# Wacky_Racer_Schematic.net
KiCad netlist of a schematic drawn in Altium Designer
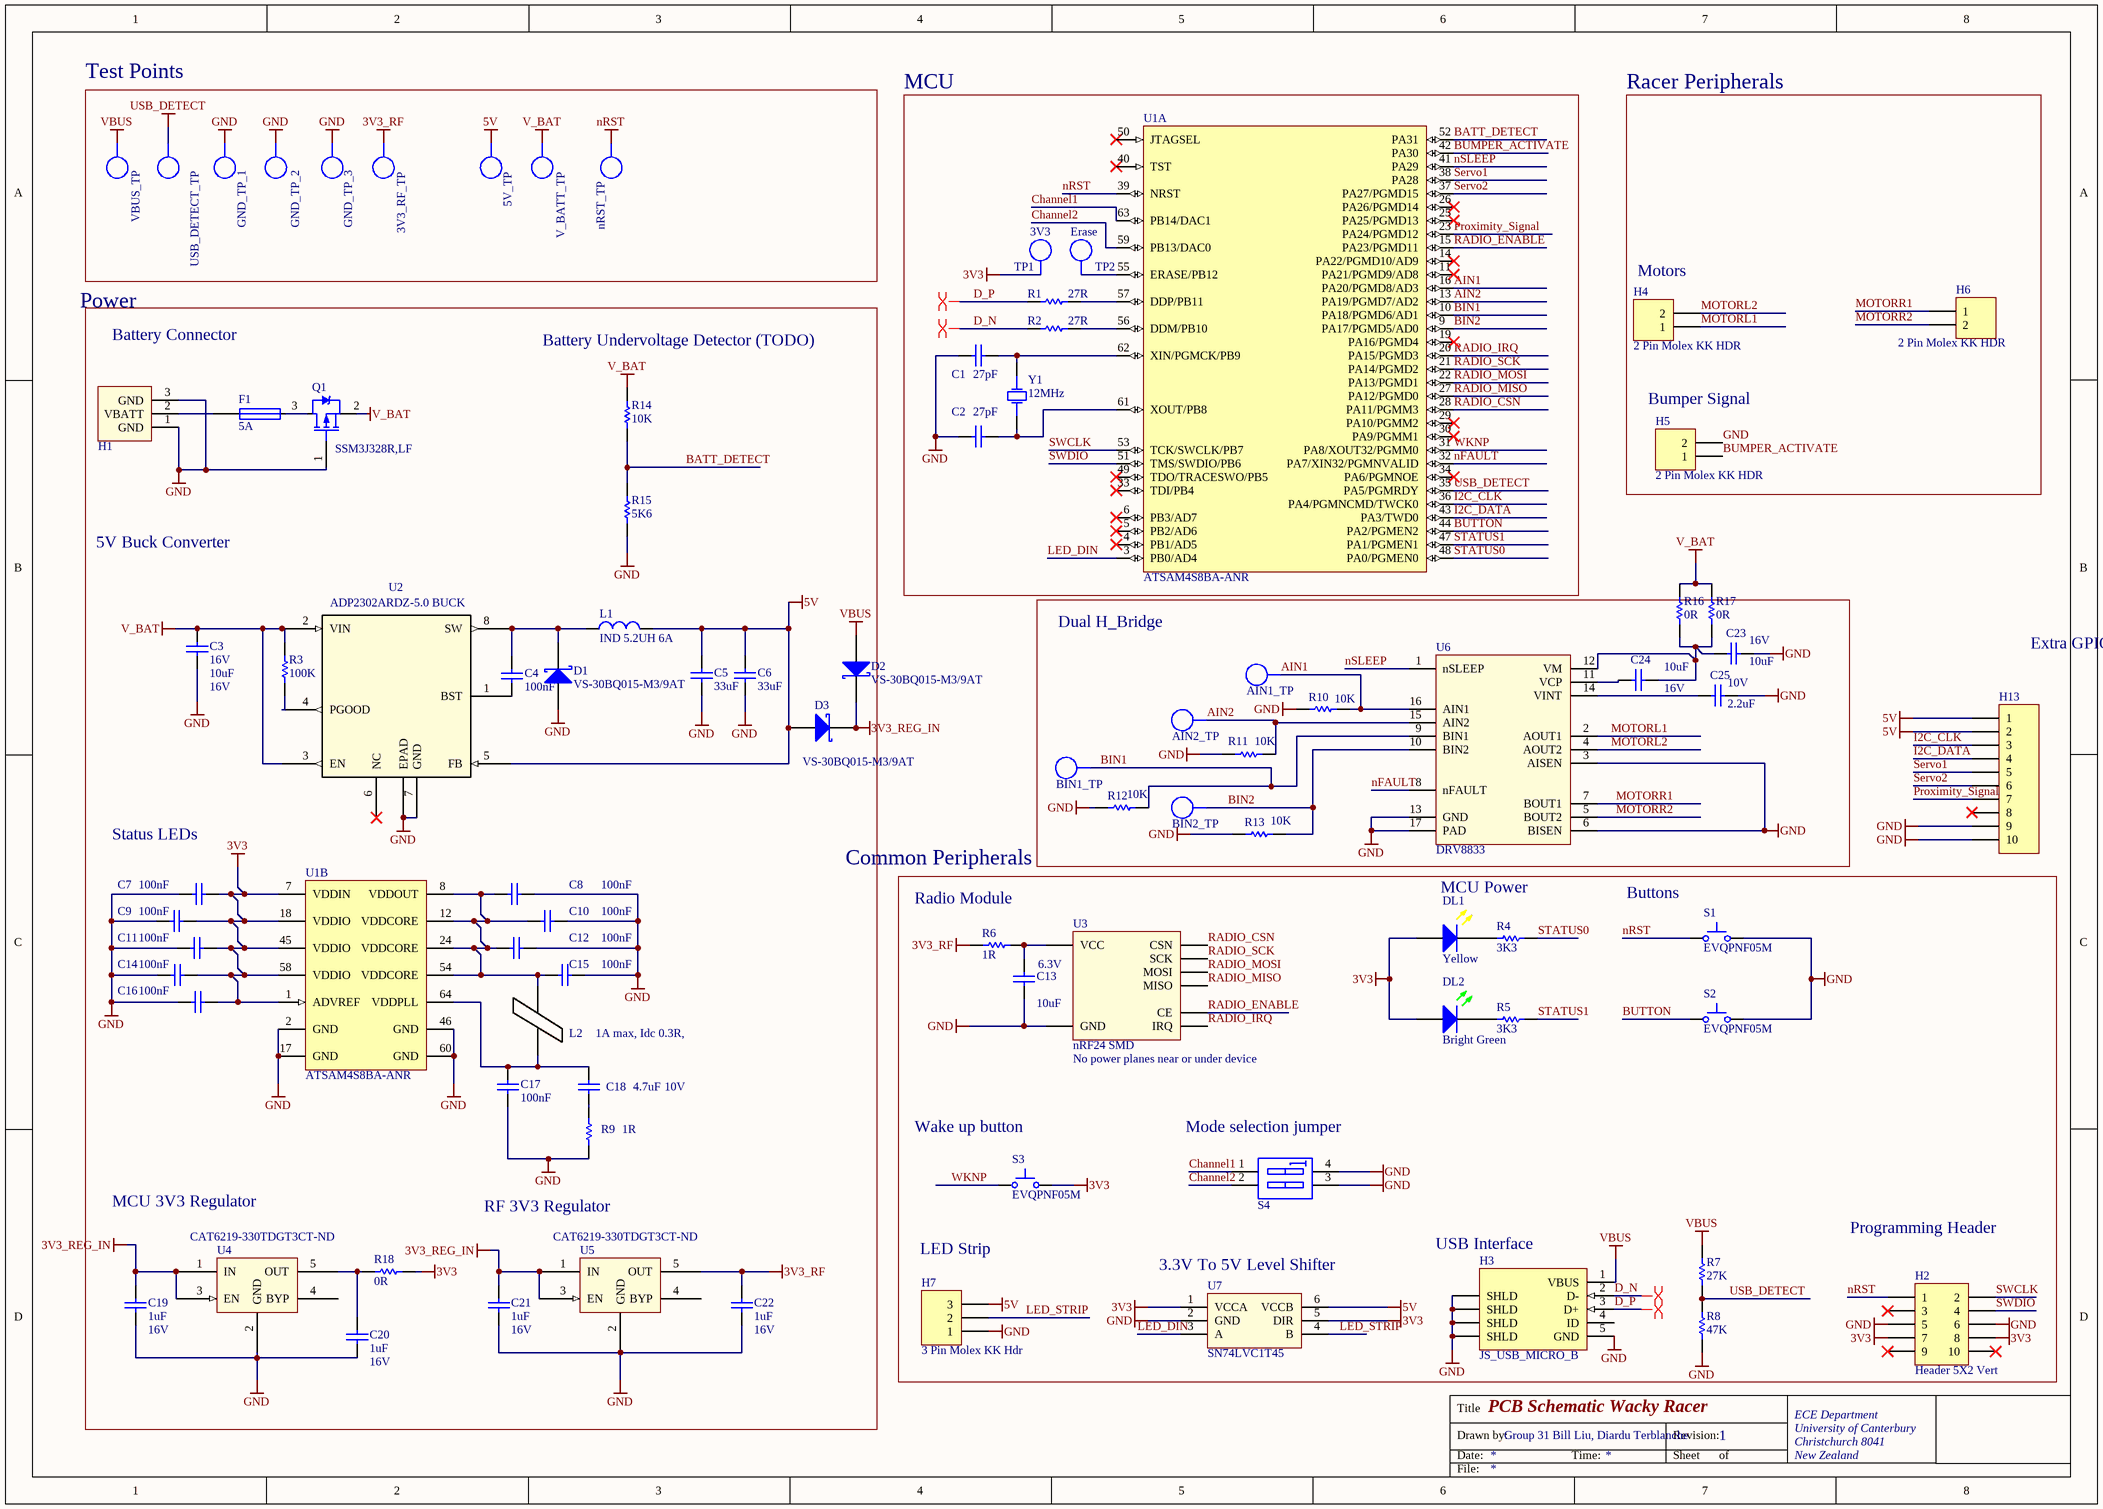
[diagram p0: Wacky Racer Schematic.schdoc]

(export (version "E")
  (design (tool "Eeschema 10.0.6"))
  (components
    (comp (ref "3V3_RF_TP")
      (value "TP")
      (footprint "TP_1206")
      (description "Test-Point 3.3x1.6x2.1mm SMD")
      (fields
        (field (name "MANUFACTURER") "Harwin Inc")
        (field (name "MANUFACTURER PART NUMBER") "S1751-46R")
      )
      (libsource (lib "ECE AD19Components_19V1") (part "TP_1206"))
    )
    (comp (ref "5V_TP")
      (value "TP")
      (footprint "TP_1206")
      (description "Test-Point 3.3x1.6x2.1mm SMD")
      (fields
        (field (name "MANUFACTURER") "Harwin Inc")
        (field (name "MANUFACTURER PART NUMBER") "S1751-46R")
      )
      (libsource (lib "ECE AD19Components_19V1") (part "TP_1206"))
    )
    (comp (ref "AIN1_TP")
      (value "TP")
      (footprint "TP_1206")
      (description "Test-Point 3.3x1.6x2.1mm SMD")
      (fields
        (field (name "MANUFACTURER") "Harwin Inc")
        (field (name "MANUFACTURER PART NUMBER") "S1751-46R")
      )
      (libsource (lib "ECE AD19Components_19V1") (part "TP_1206"))
    )
    (comp (ref "AIN2_TP")
      (value "TP")
      (footprint "TP_1206")
      (description "Test-Point 3.3x1.6x2.1mm SMD")
      (fields
        (field (name "MANUFACTURER") "Harwin Inc")
        (field (name "MANUFACTURER PART NUMBER") "S1751-46R")
      )
      (libsource (lib "ECE AD19Components_19V1") (part "TP_1206"))
    )
    (comp (ref "BIN1_TP")
      (value "TP")
      (footprint "TP_1206")
      (description "Test-Point 3.3x1.6x2.1mm SMD")
      (fields
        (field (name "MANUFACTURER") "Harwin Inc")
        (field (name "MANUFACTURER PART NUMBER") "S1751-46R")
      )
      (libsource (lib "ECE AD19Components_19V1") (part "TP_1206"))
    )
    (comp (ref "BIN2_TP")
      (value "TP")
      (footprint "TP_1206")
      (description "Test-Point 3.3x1.6x2.1mm SMD")
      (fields
        (field (name "MANUFACTURER") "Harwin Inc")
        (field (name "MANUFACTURER PART NUMBER") "S1751-46R")
      )
      (libsource (lib "ECE AD19Components_19V1") (part "TP_1206"))
    )
    (comp (ref "C1")
      (value "27pF")
      (footprint "CAPC1608L")
      (description "CAP CER 27pF NPO/COG +-5% 50V 0603")
      (libsource (lib "ECE AD19Components_19V1") (part "CC_27pF_0603"))
    )
    (comp (ref "C2")
      (value "27pF")
      (footprint "CAPC1608L")
      (description "CAP CER 27pF NPO/COG +-5% 50V 0603")
      (libsource (lib "ECE AD19Components_19V1") (part "CC_27pF_0603"))
    )
    (comp (ref "C3")
      (value "10uF")
      (footprint "CAPC2012L")
      (description "CAP CER 10uF X5R 16V 0805")
      (fields
        (field (name "MANUFACTURER") "Samsung Electro-Mechanics")
        (field (name "MANUFACTURER PART NUMBER") "CL21A106KOQNNWE")
        (field (name "VOLTAGE - RATED") "16V")
        (field (name "MAX VOLTAGE") "16V")
      )
      (libsource (lib "ENCE461AD19_19V2") (part "CC_10uF_16V_0805"))
    )
    (comp (ref "C4")
      (value "100nF")
      (footprint "CAPC1608L")
      (description "CAP CER 100nF X7R +-10% 50V 0603")
      (libsource (lib "ECE AD19Components_19V1") (part "CC_100nF_0603"))
    )
    (comp (ref "C5")
      (value "33uF")
      (footprint "CAPC2012L")
      (description "CAP CER 33uF X5R 6V3 0805")
      (fields
        (field (name "MANUFACTURER") "TDK Corporation")
        (field (name "MANUFACTURER PART NUMBER") "C2012X5R0J336M125AC")
      )
      (libsource (lib "ENCE461AD19_19V2") (part "CC_33uF_6V3_0805"))
    )
    (comp (ref "C6")
      (value "33uF")
      (footprint "CAPC2012L")
      (description "CAP CER 33uF X5R 6V3 0805")
      (fields
        (field (name "MANUFACTURER") "TDK Corporation")
        (field (name "MANUFACTURER PART NUMBER") "C2012X5R0J336M125AC")
      )
      (libsource (lib "ENCE461AD19_19V2") (part "CC_33uF_6V3_0805"))
    )
    (comp (ref "C7")
      (value "100nF")
      (footprint "CAPC1608L")
      (description "CAP CER 100nF X7R +-10% 50V 0603")
      (libsource (lib "ECE AD19Components_19V1") (part "CC_100nF_0603"))
    )
    (comp (ref "C8")
      (value "100nF")
      (footprint "CAPC1608L")
      (description "CAP CER 100nF X7R +-10% 50V 0603")
      (libsource (lib "ECE AD19Components_19V1") (part "CC_100nF_0603"))
    )
    (comp (ref "C9")
      (value "100nF")
      (footprint "CAPC1608L")
      (description "CAP CER 100nF X7R +-10% 50V 0603")
      (libsource (lib "ECE AD19Components_19V1") (part "CC_100nF_0603"))
    )
    (comp (ref "C10")
      (value "100nF")
      (footprint "CAPC1608L")
      (description "CAP CER 100nF X7R +-10% 50V 0603")
      (libsource (lib "ECE AD19Components_19V1") (part "CC_100nF_0603"))
    )
    (comp (ref "C11")
      (value "100nF")
      (footprint "CAPC1608L")
      (description "CAP CER 100nF X7R +-10% 50V 0603")
      (libsource (lib "ECE AD19Components_19V1") (part "CC_100nF_0603"))
    )
    (comp (ref "C12")
      (value "100nF")
      (footprint "CAPC1608L")
      (description "CAP CER 100nF X7R +-10% 50V 0603")
      (libsource (lib "ECE AD19Components_19V1") (part "CC_100nF_0603"))
    )
    (comp (ref "C13")
      (value "10uF")
      (footprint "CAPC1608L")
      (description "CAP CER 10UF X5R +-20% 6V3 0603")
      (fields (field (name "VOLTAGE - RATED") "6.3V"))
      (libsource (lib "ECE AD19Components_19V1") (part "CC_10uF_0603"))
    )
    (comp (ref "C14")
      (value "100nF")
      (footprint "CAPC1608L")
      (description "CAP CER 100nF X7R +-10% 50V 0603")
      (libsource (lib "ECE AD19Components_19V1") (part "CC_100nF_0603"))
    )
    (comp (ref "C15")
      (value "100nF")
      (footprint "CAPC1608L")
      (description "CAP CER 100nF X7R +-10% 50V 0603")
      (libsource (lib "ECE AD19Components_19V1") (part "CC_100nF_0603"))
    )
    (comp (ref "C16")
      (value "100nF")
      (footprint "CAPC1608L")
      (description "CAP CER 100nF X7R +-10% 50V 0603")
      (libsource (lib "ECE AD19Components_19V1") (part "CC_100nF_0603"))
    )
    (comp (ref "C17")
      (value "100nF")
      (footprint "CAPC1608L")
      (description "CAP CER 100nF X7R +-10% 50V 0603")
      (libsource (lib "ECE AD19Components_19V1") (part "CC_100nF_0603"))
    )
    (comp (ref "C18")
      (value "4.7uF")
      (footprint "CAPC1608N")
      (description "CAP CER 4.7uF X5R +-20%  10V 0603")
      (fields (field (name "MAX VOLTAGE") "10V"))
      (libsource (lib "ECE AD19Components_19V1") (part "CC_4.7uF_0603"))
    )
    (comp (ref "C19")
      (value "1uF")
      (footprint "CAPC1608L")
      (description "CAP CER 1uF Y5V -20% +80% 16V 0603")
      (fields (field (name "MAX VOLTAGE") "16V"))
      (libsource (lib "ECE AD19Components_19V1") (part "CC_1uF_0603"))
    )
    (comp (ref "C20")
      (value "1uF")
      (footprint "CAPC1608L")
      (description "CAP CER 1uF Y5V -20% +80% 16V 0603")
      (fields (field (name "MAX VOLTAGE") "16V"))
      (libsource (lib "ECE AD19Components_19V1") (part "CC_1uF_0603"))
    )
    (comp (ref "C21")
      (value "1uF")
      (footprint "CAPC1608L")
      (description "CAP CER 1uF Y5V -20% +80% 16V 0603")
      (fields (field (name "MAX VOLTAGE") "16V"))
      (libsource (lib "ECE AD19Components_19V1") (part "CC_1uF_0603"))
    )
    (comp (ref "C22")
      (value "1uF")
      (footprint "CAPC1608L")
      (description "CAP CER 1uF Y5V -20% +80% 16V 0603")
      (fields (field (name "MAX VOLTAGE") "16V"))
      (libsource (lib "ECE AD19Components_19V1") (part "CC_1uF_0603"))
    )
    (comp (ref "C23")
      (value "10uF")
      (footprint "CAPC2012L")
      (description "CAP CER 10uF X5R 16V 0805")
      (fields
        (field (name "MANUFACTURER") "Samsung Electro-Mechanics")
        (field (name "MANUFACTURER PART NUMBER") "CL21A106KOQNNWE")
        (field (name "VOLTAGE - RATED") "16V")
      )
      (libsource (lib "ENCE461AD19_19V2") (part "CC_10uF_16V_0805"))
    )
    (comp (ref "C24")
      (value "10uF")
      (footprint "CAPC2012L")
      (description "CAP CER 10uF X5R 16V 0805")
      (fields
        (field (name "MANUFACTURER") "Samsung Electro-Mechanics")
        (field (name "MANUFACTURER PART NUMBER") "CL21A106KOQNNWE")
        (field (name "VOLTAGE - RATED") "16V")
      )
      (libsource (lib "ENCE461AD19_19V2") (part "CC_10uF_16V_0805"))
    )
    (comp (ref "C25")
      (value "2.2uF")
      (footprint "CAPC1608L")
      (description "CAP CER 2.2uF X5R +-20% 10V 0603")
      (fields (field (name "MAX VOLTAGE") "10V"))
      (libsource (lib "ECE AD19Components_19V1") (part "CC_2.2uF_0603"))
    )
    (comp (ref "D1")
      (value "VS-30BQ015-M3/9AT")
      (footprint "SMC")
      (description "DIODE, SCHOTTKY, 3A, 15V, DO-214AB / SMC")
      (fields (field (name "MANUFACTURER") "Vishay Semiconductors"))
      (libsource (lib "ECE AD19Components_19V1") (part "DS_VS-30BQ015-M3"))
    )
    (comp (ref "D2")
      (value "VS-30BQ015-M3/9AT")
      (footprint "SMC")
      (description "DIODE, SCHOTTKY, 3A, 15V, DO-214AB / SMC")
      (fields (field (name "MANUFACTURER") "Vishay Semiconductors"))
      (libsource (lib "ECE AD19Components_19V1") (part "DS_VS-30BQ015-M3"))
    )
    (comp (ref "D3")
      (value "VS-30BQ015-M3/9AT")
      (footprint "SMC")
      (description "DIODE, SCHOTTKY, 3A, 15V, DO-214AB / SMC")
      (fields (field (name "MANUFACTURER") "Vishay Semiconductors"))
      (libsource (lib "ECE AD19Components_19V1") (part "DS_VS-30BQ015-M3"))
    )
    (comp (ref "DL1")
      (value "Yellow")
      (footprint "WL-SMCW0603")
      (description "LED Yellow 120mcd 0603 SMD")
      (fields
        (field (name "MANUFACTURER") "WURTH ELEKTRONIK")
        (field (name "MANUFACTURER PART NUMBER") "150060YS75000")
        (field (name "LED COLOUR") "Yellow")
      )
      (libsource (lib "ECE AD19Components_19V1") (part "DL_150060YS75000"))
    )
    (comp (ref "DL2")
      (value "Bright Green")
      (footprint "WL-SMCW0603")
      (description "LED Bright Green 40mcd 0603 SMD")
      (fields
        (field (name "MANUFACTURER") "WURTH ELEKTRONIK")
        (field (name "MANUFACTURER PART NUMBER") "150060VS75000")
        (field (name "LED COLOUR") "Bright Green")
      )
      (libsource (lib "ECE AD19Components_19V1") (part "DL_150060VS75000"))
    )
    (comp (ref "F1")
      (value "5A")
      (footprint "RESC3216N")
      (description "Fuse 5.0A Fast Acting 1206 SMD")
      (fields (field (name "MANUFACTURER PART NUMBER") "C1F5") (field (name "MANUFACTURER") "Bel TRP"))
      (libsource (lib "ECE AD19Components_19V1") (part "FS_Fuse_5.0A"))
    )
    (comp (ref "GND_TP_1")
      (value "TP")
      (footprint "TP_1206")
      (description "Test-Point 3.3x1.6x2.1mm SMD")
      (fields
        (field (name "MANUFACTURER") "Harwin Inc")
        (field (name "MANUFACTURER PART NUMBER") "S1751-46R")
      )
      (libsource (lib "ECE AD19Components_19V1") (part "TP_1206"))
    )
    (comp (ref "GND_TP_2")
      (value "TP")
      (footprint "TP_1206")
      (description "Test-Point 3.3x1.6x2.1mm SMD")
      (fields
        (field (name "MANUFACTURER") "Harwin Inc")
        (field (name "MANUFACTURER PART NUMBER") "S1751-46R")
      )
      (libsource (lib "ECE AD19Components_19V1") (part "TP_1206"))
    )
    (comp (ref "GND_TP_3")
      (value "TP")
      (footprint "TP_1206")
      (description "Test-Point 3.3x1.6x2.1mm SMD")
      (fields
        (field (name "MANUFACTURER") "Harwin Inc")
        (field (name "MANUFACTURER PART NUMBER") "S1751-46R")
      )
      (libsource (lib "ECE AD19Components_19V1") (part "TP_1206"))
    )
    (comp (ref "H1")
      (value "Battery_HEADER_3pin")
      (footprint "BATT_HEADER_3POS")
      (description "3Pin Header 2.54mm spacing")
      (libsource (lib "ENCE461AD19_19V2") (part "Battery_HEADER_3pin"))
    )
    (comp (ref "H2")
      (value "Header 5X2 Vert")
      (footprint "IDC2.54-V10D")
      (description "IDC Header, 2,54mm, 10-Pin, Vert")
      (libsource (lib "ECE AD19Components_19V1") (part "JA_HDR_IDC_5X2_VERT"))
    )
    (comp (ref "H3")
      (value "JS_USB_MICRO_B")
      (footprint "FCI_USB_10118194-0001LF")
      (description "CONN USB MICRO B RECPT SMT R/A")
      (fields (field (name "MANUFACTURER") "FCI") (field (name "MANUFACTURER PART NUMBER") "10118194-0001LF"))
      (libsource (lib "ECE AD19Components_19V1") (part "JS_USB_MICRO_B_SMT"))
    )
    (comp (ref "H4")
      (value "2 Pin Molex KK HDR")
      (footprint "MOLEX_KK_2_HDR")
      (description "CONN HEADER 2POS 2.54mm VERT_Thru Hole")
      (libsource (lib "ECE AD19Components_19V1") (part "JA_MOLEX_KK_2POS"))
    )
    (comp (ref "H5")
      (value "2 Pin Molex KK HDR")
      (footprint "MOLEX_KK_2_HDR")
      (description "CONN HEADER 2POS 2.54mm VERT_Thru Hole")
      (libsource (lib "ECE AD19Components_19V1") (part "JA_MOLEX_KK_2POS"))
    )
    (comp (ref "H6")
      (value "2 Pin Molex KK HDR")
      (footprint "MOLEX_KK_2_HDR")
      (description "CONN HEADER 2POS 2.54mm VERT_Thru Hole")
      (libsource (lib "") (part "JA_MOLEX_KK_2POS_1"))
    )
    (comp (ref "H7")
      (value "3 Pin Molex KK Hdr")
      (footprint "MOLEX_KK_3_HDR")
      (description "CONN HEADER 3POS 2.54mm VERT_Thru Hole")
      (fields (field (name "MANUFACTURER") "Molex"))
      (libsource (lib "ECE AD19Components_19V1") (part "JA_MOLEX_KK_3POS"))
    )
    (comp (ref "H13")
      (value "~")
      (footprint "MOLEX_KK_10_HDR")
      (description "CONN HEADER 10POS 2.54mm VERT_ Thru Hole")
      (libsource (lib "ECE AD19Components_19V1") (part "JA_MOLEX_KK_10POS"))
    )
    (comp (ref "L1")
      (value "IND 5.2UH 6A")
      (footprint "INDUCTOR5u2")
      (description "FIXED IND 5.2UH 6A 22 MOHM SMD")
      (fields
        (field (name "MANUFACTURER") "Sumida America Components Inc.")
        (field (name "MANUFACTURER PART NUMBER") "CDRH104RNP-5R2NC")
      )
      (libsource (lib "ENCE461AD19_19V2") (part "CDRH104RNP-5R2NC"))
    )
    (comp (ref "L2")
      (value "1A max, Idc 0.3R,")
      (footprint "INDC3216L")
      (description "Ferrite Bead, Rdc 0.3R, Z100MHZ 600R, Imax 1A, SMD 1206")
      (fields
        (field (name "MANUFACTURER") "FAIR-RITE")
        (field (name "MANUFACTURER PART NUMBER") "2512066017Y1")
      )
      (libsource (lib "ECE AD19Components_19V1") (part "IN_Ferrite-Bead"))
    )
    (comp (ref "nRST_TP")
      (value "TP")
      (footprint "TP_1206")
      (description "Test-Point 3.3x1.6x2.1mm SMD")
      (fields
        (field (name "MANUFACTURER") "Harwin Inc")
        (field (name "MANUFACTURER PART NUMBER") "S1751-46R")
      )
      (libsource (lib "ECE AD19Components_19V1") (part "TP_1206"))
    )
    (comp (ref "Q1")
      (value "SSM3J328R,LF")
      (footprint "SOT23_L")
      (description "MOSFET P-CH 20V 6A SOT23-3")
      (fields
        (field (name "MANUFACTURER") "Toshiba")
        (field (name "MANUFACTURER PART NUMBER") "SSM3J328R,LF")
      )
      (libsource (lib "ECE AD19Components_19V1") (part "TM_SSM3J328R"))
    )
    (comp (ref "R1")
      (value "27R")
      (footprint "RESC1608L")
      (description "RES 27 OHM 1/10W 5% 0603 SMD")
      (libsource (lib "ECE AD19Components_19V1") (part "RS_27R"))
    )
    (comp (ref "R2")
      (value "27R")
      (footprint "RESC1608L")
      (description "RES 27 OHM 1/10W 5% 0603 SMD")
      (libsource (lib "ECE AD19Components_19V1") (part "RS_27R"))
    )
    (comp (ref "R3")
      (value "100K")
      (footprint "RESC1608L")
      (description "RES 100K OHM 1/10W 5% 0603 SMD")
      (libsource (lib "ECE AD19Components_19V1") (part "RS_100K"))
    )
    (comp (ref "R4")
      (value "3K3")
      (footprint "RESC1608L")
      (description "RES 3.3K OHM 1/10W 5% 0603 SMD")
      (libsource (lib "ECE AD19Components_19V1") (part "RS_3K3"))
    )
    (comp (ref "R5")
      (value "3K3")
      (footprint "RESC1608L")
      (description "RES 3.3K OHM 1/10W 5% 0603 SMD")
      (libsource (lib "ECE AD19Components_19V1") (part "RS_3K3"))
    )
    (comp (ref "R6")
      (value "1R")
      (footprint "RESC3216L")
      (description "RES 1R OHM 1/4W 5% 1206 SMD")
      (libsource (lib "ECE AD19Components_19V1") (part "RT_1R"))
    )
    (comp (ref "R7")
      (value "27K")
      (footprint "RESC1608L")
      (description "RES 27K OHM 1/10W 5% 0603 SMD")
      (libsource (lib "ECE AD19Components_19V1") (part "RS_27K"))
    )
    (comp (ref "R8")
      (value "47K")
      (footprint "RESC1608N")
      (description "RES 47.0K OHM 1/10W 5% 0603 SMD")
      (libsource (lib "ECE AD19Components_19V1") (part "RS_47K"))
    )
    (comp (ref "R9")
      (value "1R")
      (footprint "RESC3216L")
      (description "RES 1R OHM 1/4W 5% 1206 SMD")
      (libsource (lib "ECE AD19Components_19V1") (part "RT_1R"))
    )
    (comp (ref "R10")
      (value "10K")
      (footprint "RESC1608L")
      (description "RES 10.0K OHM 1/10W 5% 0603 SMD")
      (libsource (lib "ECE AD19Components_19V1") (part "RS_10K"))
    )
    (comp (ref "R11")
      (value "10K")
      (footprint "RESC1608L")
      (description "RES 10.0K OHM 1/10W 5% 0603 SMD")
      (libsource (lib "ECE AD19Components_19V1") (part "RS_10K"))
    )
    (comp (ref "R12")
      (value "10K")
      (footprint "RESC1608L")
      (description "RES 10.0K OHM 1/10W 5% 0603 SMD")
      (libsource (lib "ECE AD19Components_19V1") (part "RS_10K"))
    )
    (comp (ref "R13")
      (value "10K")
      (footprint "RESC1608L")
      (description "RES 10.0K OHM 1/10W 5% 0603 SMD")
      (libsource (lib "ECE AD19Components_19V1") (part "RS_10K"))
    )
    (comp (ref "R14")
      (value "10K")
      (footprint "RESC1608L")
      (description "RES 10.0K OHM 1/10W 5% 0603 SMD")
      (libsource (lib "ECE AD19Components_19V1") (part "RS_10K"))
    )
    (comp (ref "R15")
      (value "5K6")
      (footprint "RESC1608L")
      (description "RES 5.6K OHM 1/10W 5% 0603 SMD")
      (libsource (lib "ECE AD19Components_19V1") (part "RS_5K6"))
    )
    (comp (ref "R16")
      (value "0R")
      (footprint "RESC1608L")
      (description "RES 0.0 OHM 1/10W 5% 0603 SMD")
      (libsource (lib "ECE AD19Components_19V1") (part "RS_0R0"))
    )
    (comp (ref "R17")
      (value "0R")
      (footprint "RESC1608L")
      (description "RES 0.0 OHM 1/10W 5% 0603 SMD")
      (libsource (lib "ECE AD19Components_19V1") (part "RS_0R0"))
    )
    (comp (ref "R18")
      (value "0R")
      (footprint "RESC1608L")
      (description "RES 0.0 OHM 1/10W 5% 0603 SMD")
      (libsource (lib "ECE AD19Components_19V1") (part "RS_0R0"))
    )
    (comp (ref "S1")
      (value "EVQPNF05M")
      (footprint "EVQPNF05M")
      (description "Panasonic 6 x 3.5mm SMD Light Touch Switch Type SMD")
      (fields (field (name "MANUFACTURER") "Panasonic"))
      (libsource (lib "ECE AD19Components_19V1") (part "WS_EVQPNF05M"))
    )
    (comp (ref "S2")
      (value "EVQPNF05M")
      (footprint "EVQPNF05M")
      (description "Panasonic 6 x 3.5mm SMD Light Touch Switch Type SMD")
      (fields (field (name "MANUFACTURER") "Panasonic"))
      (libsource (lib "ECE AD19Components_19V1") (part "WS_EVQPNF05M"))
    )
    (comp (ref "S3")
      (value "EVQPNF05M")
      (footprint "EVQPNF05M")
      (description "Panasonic 6 x 3.5mm SMD Light Touch Switch Type SMD")
      (fields (field (name "MANUFACTURER") "Panasonic"))
      (libsource (lib "ECE AD19Components_19V1") (part "WS_EVQPNF05M"))
    )
    (comp (ref "S4")
      (value "WS_SW DIP-2")
      (footprint "DIP_SW_2WAY_SMD")
      (description "DIP Switch, 2 Position, SPST SMD")
      (fields
        (field (name "MANUFACTURER") "OMRON ELECTRONIC COMPONENTS")
        (field (name "MANUFACTURER PART NUMBER") "A6SN-2101")
      )
      (libsource (lib "ECE AD19Components_19V1") (part "WS_SW DIP-2"))
    )
    (comp (ref "TP1")
      (value "3V3")
      (footprint "TP_1206")
      (description "Test-Point 3.3x1.6x2.1mm SMD")
      (fields
        (field (name "MANUFACTURER") "Harwin Inc")
        (field (name "MANUFACTURER PART NUMBER") "S1751-46R")
      )
      (libsource (lib "ECE AD19Components_19V1") (part "TP_1206"))
    )
    (comp (ref "TP2")
      (value "Erase")
      (footprint "TP_1206")
      (description "Test-Point 3.3x1.6x2.1mm SMD")
      (fields
        (field (name "MANUFACTURER") "Harwin Inc")
        (field (name "MANUFACTURER PART NUMBER") "S1751-46R")
      )
      (libsource (lib "ECE AD19Components_19V1") (part "TP_1206"))
    )
    (comp (ref "U1")
      (value "ATSAM4S8BA-ANR")
      (footprint "LQFP64_L")
      (description "IC MCU 32BIT 512KB FLASH 64LQFP")
      (fields (field (name "MANUFACTURER") "Atmel"))
      (libsource (lib "ECE AD19Components_19V1") (part "SE_ATSAM4S16BA-MU"))
    )
    (comp (ref "U2")
      (value "ADP2302ARDZ-5.0 BUCK")
      (footprint "RD_8_1")
      (description "IC REG BUCK 5V 2A 8SOIC")
      (fields (field (name "MANUFACTURER_PART_NUMBER") "ADP2302ARDZ-5.0-R7"))
      (libsource (lib "ENCE461AD19_19V2") (part "ADP2302ARDZ-5.0-R7"))
    )
    (comp (ref "U3")
      (value "nRF24 SMD")
      (footprint "NRF24")
      (description "nRF24 SMD Module")
      (fields (field (name "WARNING") "No power planes near or under device"))
      (libsource (lib "ENCE461AD19_19V2") (part "NRF24"))
    )
    (comp (ref "U4")
      (value "CAT6219-330TDGT3")
      (footprint "SOT95P280X145-5N")
      (description "IC REG LIN 3.3V 500MA TSOT23-5")
      (fields
        (field (name "BASE PART NUMBER") "CAT6219")
        (field (name "SUPPLIER PART NUMBER") "CAT6219-330TDGT3CT-ND")
      )
      (libsource (lib "ENCE461AD19_19V2") (part "SV_CAT6219-330TDGT3"))
    )
    (comp (ref "U5")
      (value "CAT6219-330TDGT3")
      (footprint "SOT95P280X145-5N")
      (description "IC REG LIN 3.3V 500MA TSOT23-5")
      (fields
        (field (name "BASE PART NUMBER") "CAT6219")
        (field (name "SUPPLIER PART NUMBER") "CAT6219-330TDGT3CT-ND")
      )
      (libsource (lib "ENCE461AD19_19V2") (part "SV_CAT6219-330TDGT3"))
    )
    (comp (ref "U6")
      (value "DRV8833")
      (footprint "HTSOP16")
      (description "Dual H-Bridge Motor Driver 1.5A")
      (libsource (lib "ENCE461AD19_19V2") (part "DRV8833"))
    )
    (comp (ref "U7")
      (value "SN74LVC1T45")
      (footprint "SOT23-6_N")
      (description "1.8V - 5V level converter")
      (libsource (lib "ENCE461_extras_2020") (part "SN74LVC1T45"))
    )
    (comp (ref "USB_DETECT_TP")
      (value "TP")
      (footprint "TP_1206")
      (description "Test-Point 3.3x1.6x2.1mm SMD")
      (fields
        (field (name "MANUFACTURER") "Harwin Inc")
        (field (name "MANUFACTURER PART NUMBER") "S1751-46R")
      )
      (libsource (lib "ECE AD19Components_19V1") (part "TP_1206"))
    )
    (comp (ref "VBUS_TP")
      (value "TP")
      (footprint "TP_1206")
      (description "Test-Point 3.3x1.6x2.1mm SMD")
      (fields
        (field (name "MANUFACTURER") "Harwin Inc")
        (field (name "MANUFACTURER PART NUMBER") "S1751-46R")
      )
      (libsource (lib "ECE AD19Components_19V1") (part "TP_1206"))
    )
    (comp (ref "V_BATT_TP")
      (value "TP")
      (footprint "TP_1206")
      (description "Test-Point 3.3x1.6x2.1mm SMD")
      (fields
        (field (name "MANUFACTURER") "Harwin Inc")
        (field (name "MANUFACTURER PART NUMBER") "S1751-46R")
      )
      (libsource (lib "ECE AD19Components_19V1") (part "TP_1206"))
    )
    (comp (ref "Y1")
      (value "12MHz")
      (footprint "6.0X3.5-4")
      (description "CRYSTAL 12MHZ 18PF 6X3.5mm SMD")
      (fields
        (field (name "MANUFACTURER") "CTS-Frequency Controls")
        (field (name "MANUFACTURER PART NUMBER") "406C35D12M00000")
        (field (name "FREQUENCY") "12MHz")
      )
      (libsource (lib "ECE AD19Components_19V1") (part "XT_CRYSTAL_12MHz_18pF"))
    )
  )
  (nets
    (net (code "2") (name "/AIN1") (class "Default")
      (node (ref "AIN1_TP") (pin "1") (pinfunction "1_1") (pintype "passive"))
      (node (ref "R10") (pin "2") (pinfunction "2_2") (pintype "passive"))
      (node (ref "U1") (pin "16") (pinfunction "PA20/PGMD8/AD3_16") (pintype "bidirectional"))
      (node (ref "U6") (pin "16") (pinfunction "AIN1_16") (pintype "passive"))
    )
    (net (code "3") (name "/AIN2") (class "Default")
      (node (ref "AIN2_TP") (pin "1") (pinfunction "1_1") (pintype "passive"))
      (node (ref "R11") (pin "2") (pinfunction "2_2") (pintype "passive"))
      (node (ref "U1") (pin "13") (pinfunction "PA19/PGMD7/AD2_13") (pintype "bidirectional"))
      (node (ref "U6") (pin "15") (pinfunction "AIN2_15") (pintype "passive"))
    )
    (net (code "4") (name "/BATT_DETECT") (class "Default")
      (node (ref "R14") (pin "1") (pinfunction "1_1") (pintype "passive"))
      (node (ref "R15") (pin "2") (pinfunction "2_2") (pintype "passive"))
      (node (ref "U1") (pin "52") (pinfunction "PA31_52") (pintype "bidirectional"))
    )
    (net (code "5") (name "/BIN1") (class "Default")
      (node (ref "BIN1_TP") (pin "1") (pinfunction "1_1") (pintype "passive"))
      (node (ref "R12") (pin "2") (pinfunction "2_2") (pintype "passive"))
      (node (ref "U1") (pin "10") (pinfunction "PA18/PGMD6/AD1_10") (pintype "bidirectional"))
      (node (ref "U6") (pin "9") (pinfunction "BIN1_9") (pintype "passive"))
    )
    (net (code "6") (name "/BIN2") (class "Default")
      (node (ref "BIN2_TP") (pin "1") (pinfunction "1_1") (pintype "passive"))
      (node (ref "R13") (pin "2") (pinfunction "2_2") (pintype "passive"))
      (node (ref "U1") (pin "9") (pinfunction "PA17/PGMD5/AD0_9") (pintype "bidirectional"))
      (node (ref "U6") (pin "10") (pinfunction "BIN2_10") (pintype "passive"))
    )
    (net (code "7") (name "/BUMPER_ACTIVATE") (class "Default")
      (node (ref "H5") (pin "1") (pinfunction "1_1") (pintype "passive"))
      (node (ref "U1") (pin "42") (pinfunction "PA30_42") (pintype "bidirectional"))
    )
    (net (code "8") (name "/BUTTON") (class "Default")
      (node (ref "S2") (pin "1") (pintype "passive"))
      (node (ref "U1") (pin "44") (pinfunction "PA2/PGMEN2_44") (pintype "bidirectional"))
    )
    (net (code "9") (name "/Channel1") (class "Default")
      (node (ref "S4") (pin "1") (pinfunction "A1_1") (pintype "passive"))
      (node (ref "U1") (pin "63") (pinfunction "PB14/DAC1_63") (pintype "bidirectional"))
    )
    (net (code "10") (name "/Channel2") (class "Default")
      (node (ref "S4") (pin "2") (pinfunction "A2_2") (pintype "passive"))
      (node (ref "U1") (pin "59") (pinfunction "PB13/DAC0_59") (pintype "bidirectional"))
    )
    (net (code "11") (name "/D_N") (class "Default")
      (node (ref "H3") (pin "2") (pinfunction "D-_2") (pintype "input"))
      (node (ref "R2") (pin "1") (pinfunction "1_1") (pintype "passive"))
    )
    (net (code "12") (name "/D_P") (class "Default")
      (node (ref "H3") (pin "3") (pinfunction "D+_3") (pintype "input"))
      (node (ref "R1") (pin "1") (pinfunction "1_1") (pintype "passive"))
    )
    (net (code "13") (name "/I2C_CLK") (class "Default")
      (node (ref "H13") (pin "3") (pinfunction "3_3") (pintype "passive"))
      (node (ref "U1") (pin "36") (pinfunction "PA4/PGMNCMD/TWCK0_36") (pintype "bidirectional"))
    )
    (net (code "14") (name "/I2C_DATA") (class "Default")
      (node (ref "H13") (pin "4") (pinfunction "4_4") (pintype "passive"))
      (node (ref "U1") (pin "43") (pinfunction "PA3/TWD0_43") (pintype "bidirectional"))
    )
    (net (code "15") (name "/LED_DIN") (class "Default")
      (node (ref "U1") (pin "3") (pinfunction "PB0/AD4_3") (pintype "bidirectional"))
      (node (ref "U7") (pin "3") (pinfunction "A_3") (pintype "passive"))
    )
    (net (code "16") (name "/LED_STRIP") (class "Default")
      (node (ref "H7") (pin "2") (pinfunction "2_2") (pintype "passive"))
      (node (ref "U7") (pin "4") (pinfunction "B_4") (pintype "passive"))
    )
    (net (code "17") (name "/MOTORL1") (class "Default")
      (node (ref "H4") (pin "1") (pinfunction "1_1") (pintype "passive"))
      (node (ref "U6") (pin "2") (pinfunction "AOUT1_2") (pintype "passive"))
    )
    (net (code "18") (name "/MOTORL2") (class "Default")
      (node (ref "H4") (pin "2") (pinfunction "2_2") (pintype "passive"))
      (node (ref "U6") (pin "4") (pinfunction "AOUT2_4") (pintype "passive"))
    )
    (net (code "19") (name "/MOTORR1") (class "Default")
      (node (ref "H6") (pin "1") (pinfunction "1_1") (pintype "passive"))
      (node (ref "U6") (pin "7") (pinfunction "BOUT1_7") (pintype "passive"))
    )
    (net (code "20") (name "/MOTORR2") (class "Default")
      (node (ref "H6") (pin "2") (pinfunction "2_2") (pintype "passive"))
      (node (ref "U6") (pin "5") (pinfunction "BOUT2_5") (pintype "passive"))
    )
    (net (code "21") (name "/Proximity_Signal") (class "Default")
      (node (ref "H13") (pin "7") (pinfunction "7_7") (pintype "passive"))
      (node (ref "U1") (pin "23") (pinfunction "PA24/PGMD12_23") (pintype "bidirectional"))
    )
    (net (code "22") (name "/RADIO_CSN") (class "Default")
      (node (ref "U1") (pin "28") (pinfunction "PA11/PGMM3_28") (pintype "bidirectional"))
      (node (ref "U3") (pin "4") (pinfunction "CSN_4") (pintype "passive"))
    )
    (net (code "23") (name "/RADIO_ENABLE") (class "Default")
      (node (ref "U1") (pin "15") (pinfunction "PA23/PGMD11_15") (pintype "bidirectional"))
      (node (ref "U3") (pin "3") (pinfunction "CE_3") (pintype "passive"))
    )
    (net (code "24") (name "/RADIO_IRQ") (class "Default")
      (node (ref "U1") (pin "20") (pinfunction "PA15/PGMD3_20") (pintype "bidirectional"))
      (node (ref "U3") (pin "8") (pinfunction "IRQ_8") (pintype "passive"))
    )
    (net (code "25") (name "/RADIO_MISO") (class "Default")
      (node (ref "U1") (pin "27") (pinfunction "PA12/PGMD0_27") (pintype "bidirectional"))
      (node (ref "U3") (pin "7") (pinfunction "MISO_7") (pintype "passive"))
    )
    (net (code "26") (name "/RADIO_MOSI") (class "Default")
      (node (ref "U1") (pin "22") (pinfunction "PA13/PGMD1_22") (pintype "bidirectional"))
      (node (ref "U3") (pin "6") (pinfunction "MOSI_6") (pintype "passive"))
    )
    (net (code "27") (name "/RADIO_SCK") (class "Default")
      (node (ref "U1") (pin "21") (pinfunction "PA14/PGMD2_21") (pintype "bidirectional"))
      (node (ref "U3") (pin "5") (pinfunction "SCK_5") (pintype "passive"))
    )
    (net (code "28") (name "/STATUS0") (class "Default")
      (node (ref "R4") (pin "2") (pinfunction "2_2") (pintype "passive"))
      (node (ref "U1") (pin "48") (pinfunction "PA0/PGMEN0_48") (pintype "bidirectional"))
    )
    (net (code "29") (name "/STATUS1") (class "Default")
      (node (ref "R5") (pin "2") (pinfunction "2_2") (pintype "passive"))
      (node (ref "U1") (pin "47") (pinfunction "PA1/PGMEN1_47") (pintype "bidirectional"))
    )
    (net (code "30") (name "/SWCLK") (class "Default")
      (node (ref "H2") (pin "2") (pinfunction "2_2") (pintype "passive"))
      (node (ref "U1") (pin "53") (pinfunction "TCK/SWCLK/PB7_53") (pintype "bidirectional"))
    )
    (net (code "31") (name "/SWDIO") (class "Default")
      (node (ref "H2") (pin "4") (pinfunction "4_4") (pintype "passive"))
      (node (ref "U1") (pin "51") (pinfunction "TMS/SWDIO/PB6_51") (pintype "bidirectional"))
    )
    (net (code "32") (name "/Servo1") (class "Default")
      (node (ref "H13") (pin "5") (pinfunction "5_5") (pintype "passive"))
      (node (ref "U1") (pin "38") (pinfunction "PA28_38") (pintype "bidirectional"))
    )
    (net (code "33") (name "/Servo2") (class "Default")
      (node (ref "H13") (pin "6") (pinfunction "6_6") (pintype "passive"))
      (node (ref "U1") (pin "37") (pinfunction "PA27/PGMD15_37") (pintype "bidirectional"))
    )
    (net (code "34") (name "/WKNP") (class "Default")
      (node (ref "S3") (pin "1") (pintype "passive"))
      (node (ref "U1") (pin "31") (pinfunction "PA8/XOUT32/PGMM0_31") (pintype "bidirectional"))
    )
    (net (code "35") (name "/nFAULT") (class "Default")
      (node (ref "U1") (pin "32") (pinfunction "PA7/XIN32/PGMNVALID_32") (pintype "bidirectional"))
      (node (ref "U6") (pin "8") (pinfunction "nFAULT_8") (pintype "passive"))
    )
    (net (code "36") (name "/nSLEEP") (class "Default")
      (node (ref "U1") (pin "41") (pinfunction "PA29_41") (pintype "bidirectional"))
      (node (ref "U6") (pin "1") (pinfunction "nSLEEP_1") (pintype "passive"))
    )
    (net (code "37") (name "3V3") (class "Default")
      (node (ref "C11") (pin "2") (pinfunction "2_2") (pintype "passive"))
      (node (ref "C14") (pin "2") (pinfunction "2_2") (pintype "passive"))
      (node (ref "C16") (pin "2") (pinfunction "2_2") (pintype "passive"))
      (node (ref "C7") (pin "2") (pinfunction "2_2") (pintype "passive"))
      (node (ref "C9") (pin "2") (pinfunction "2_2") (pintype "passive"))
      (node (ref "DL1") (pin "2") (pinfunction "A_2") (pintype "passive"))
      (node (ref "DL2") (pin "2") (pinfunction "A_2") (pintype "passive"))
      (node (ref "H2") (pin "7") (pinfunction "7_7") (pintype "passive"))
      (node (ref "H2") (pin "8") (pinfunction "8_8") (pintype "passive"))
      (node (ref "R18") (pin "2") (pinfunction "2_2") (pintype "passive"))
      (node (ref "S3") (pin "2") (pintype "passive"))
      (node (ref "TP1") (pin "1") (pinfunction "1_1") (pintype "passive"))
      (node (ref "U1") (pin "1") (pinfunction "ADVREF_1") (pintype "input"))
      (node (ref "U1") (pin "18") (pinfunction "VDDIO_18") (pintype "power_in"))
      (node (ref "U1") (pin "45") (pinfunction "VDDIO_45") (pintype "power_in"))
      (node (ref "U1") (pin "58") (pinfunction "VDDIO_58") (pintype "power_in"))
      (node (ref "U1") (pin "7") (pinfunction "VDDIN_7") (pintype "power_in"))
      (node (ref "U7") (pin "1") (pinfunction "VCCA_1") (pintype "passive"))
      (node (ref "U7") (pin "5") (pinfunction "DIR_5") (pintype "passive"))
    )
    (net (code "38") (name "3V3_REG_IN") (class "Default")
      (node (ref "C19") (pin "2") (pinfunction "2_2") (pintype "passive"))
      (node (ref "C21") (pin "2") (pinfunction "2_2") (pintype "passive"))
      (node (ref "D2") (pin "2") (pinfunction "K_2") (pintype "passive"))
      (node (ref "D3") (pin "2") (pinfunction "K_2") (pintype "passive"))
      (node (ref "U4") (pin "1") (pinfunction "IN_1") (pintype "power_in"))
      (node (ref "U4") (pin "3") (pinfunction "EN_3") (pintype "input"))
      (node (ref "U5") (pin "1") (pinfunction "IN_1") (pintype "power_in"))
      (node (ref "U5") (pin "3") (pinfunction "EN_3") (pintype "input"))
    )
    (net (code "39") (name "3V3_RF") (class "Default")
      (node (ref "3V3_RF_TP") (pin "1") (pinfunction "1_1") (pintype "passive"))
      (node (ref "C22") (pin "2") (pinfunction "2_2") (pintype "passive"))
      (node (ref "R6") (pin "1") (pinfunction "1_1") (pintype "passive"))
      (node (ref "U5") (pin "5") (pinfunction "OUT_5") (pintype "power_in"))
    )
    (net (code "40") (name "5V") (class "Default")
      (node (ref "5V_TP") (pin "1") (pinfunction "1_1") (pintype "passive"))
      (node (ref "C5") (pin "2") (pinfunction "2_2") (pintype "passive"))
      (node (ref "C6") (pin "2") (pinfunction "2_2") (pintype "passive"))
      (node (ref "D3") (pin "1") (pinfunction "A_1") (pintype "passive"))
      (node (ref "H13") (pin "1") (pinfunction "1_1") (pintype "passive"))
      (node (ref "H13") (pin "2") (pinfunction "2_2") (pintype "passive"))
      (node (ref "H7") (pin "3") (pinfunction "3_3") (pintype "passive"))
      (node (ref "L1") (pin "2") (pintype "passive"))
      (node (ref "U2") (pin "5") (pinfunction "FB_5") (pintype "input"))
      (node (ref "U7") (pin "6") (pinfunction "VCCB_6") (pintype "passive"))
    )
    (net (code "41") (name "GND") (class "Default")
      (node (ref "C1") (pin "1") (pinfunction "1_1") (pintype "passive"))
      (node (ref "C10") (pin "2") (pinfunction "2_2") (pintype "passive"))
      (node (ref "C11") (pin "1") (pinfunction "1_1") (pintype "passive"))
      (node (ref "C12") (pin "2") (pinfunction "2_2") (pintype "passive"))
      (node (ref "C13") (pin "1") (pinfunction "1_1") (pintype "passive"))
      (node (ref "C14") (pin "1") (pinfunction "1_1") (pintype "passive"))
      (node (ref "C15") (pin "2") (pinfunction "2_2") (pintype "passive"))
      (node (ref "C16") (pin "1") (pinfunction "1_1") (pintype "passive"))
      (node (ref "C17") (pin "1") (pinfunction "1_1") (pintype "passive"))
      (node (ref "C19") (pin "1") (pinfunction "1_1") (pintype "passive"))
      (node (ref "C2") (pin "1") (pinfunction "1_1") (pintype "passive"))
      (node (ref "C20") (pin "1") (pinfunction "1_1") (pintype "passive"))
      (node (ref "C21") (pin "1") (pinfunction "1_1") (pintype "passive"))
      (node (ref "C22") (pin "1") (pinfunction "1_1") (pintype "passive"))
      (node (ref "C23") (pin "2") (pinfunction "2_2") (pintype "passive"))
      (node (ref "C25") (pin "2") (pinfunction "2_2") (pintype "passive"))
      (node (ref "C3") (pin "1") (pinfunction "1_1") (pintype "passive"))
      (node (ref "C5") (pin "1") (pinfunction "1_1") (pintype "passive"))
      (node (ref "C6") (pin "1") (pinfunction "1_1") (pintype "passive"))
      (node (ref "C7") (pin "1") (pinfunction "1_1") (pintype "passive"))
      (node (ref "C8") (pin "2") (pinfunction "2_2") (pintype "passive"))
      (node (ref "C9") (pin "1") (pinfunction "1_1") (pintype "passive"))
      (node (ref "D1") (pin "1") (pinfunction "A_1") (pintype "passive"))
      (node (ref "GND_TP_1") (pin "1") (pinfunction "1_1") (pintype "passive"))
      (node (ref "GND_TP_2") (pin "1") (pinfunction "1_1") (pintype "passive"))
      (node (ref "GND_TP_3") (pin "1") (pinfunction "1_1") (pintype "passive"))
      (node (ref "H1") (pin "1") (pinfunction "GND_1") (pintype "passive"))
      (node (ref "H1") (pin "3") (pinfunction "GND_3") (pintype "passive"))
      (node (ref "H13") (pin "10") (pinfunction "10_10") (pintype "passive"))
      (node (ref "H13") (pin "9") (pinfunction "9_9") (pintype "passive"))
      (node (ref "H2") (pin "5") (pinfunction "5_5") (pintype "passive"))
      (node (ref "H2") (pin "6") (pinfunction "6_6") (pintype "passive"))
      (node (ref "H3") (pin "5") (pinfunction "GND_5") (pintype "passive"))
      (node (ref "H3") (pin "6") (pinfunction "SHLD_6") (pintype "passive"))
      (node (ref "H5") (pin "2") (pinfunction "2_2") (pintype "passive"))
      (node (ref "H7") (pin "1") (pinfunction "1_1") (pintype "passive"))
      (node (ref "Q1") (pin "1") (pinfunction "1_1") (pintype "passive"))
      (node (ref "R10") (pin "1") (pinfunction "1_1") (pintype "passive"))
      (node (ref "R11") (pin "1") (pinfunction "1_1") (pintype "passive"))
      (node (ref "R12") (pin "1") (pinfunction "1_1") (pintype "passive"))
      (node (ref "R13") (pin "1") (pinfunction "1_1") (pintype "passive"))
      (node (ref "R15") (pin "1") (pinfunction "1_1") (pintype "passive"))
      (node (ref "R8") (pin "1") (pinfunction "1_1") (pintype "passive"))
      (node (ref "R9") (pin "1") (pinfunction "1_1") (pintype "passive"))
      (node (ref "S1") (pin "2") (pintype "passive"))
      (node (ref "S2") (pin "2") (pintype "passive"))
      (node (ref "S4") (pin "3") (pinfunction "B2_3") (pintype "passive"))
      (node (ref "S4") (pin "4") (pinfunction "B1_4") (pintype "passive"))
      (node (ref "U1") (pin "17") (pinfunction "GND_17") (pintype "power_in"))
      (node (ref "U1") (pin "2") (pinfunction "GND_2") (pintype "power_in"))
      (node (ref "U1") (pin "46") (pinfunction "GND_46") (pintype "power_in"))
      (node (ref "U1") (pin "60") (pinfunction "GND_60") (pintype "power_in"))
      (node (ref "U2") (pin "7") (pinfunction "GND_7") (pintype "power_in"))
      (node (ref "U2") (pin "EPAD") (pinfunction "EPAD_EPAD") (pintype "passive"))
      (node (ref "U3") (pin "2") (pinfunction "GND_2") (pintype "passive"))
      (node (ref "U4") (pin "2") (pinfunction "GND_2") (pintype "power_in"))
      (node (ref "U5") (pin "2") (pinfunction "GND_2") (pintype "power_in"))
      (node (ref "U6") (pin "13") (pinfunction "GND_13") (pintype "passive"))
      (node (ref "U6") (pin "17") (pinfunction "PAD_17") (pintype "passive"))
      (node (ref "U6") (pin "3") (pinfunction "AISEN_3") (pintype "passive"))
      (node (ref "U6") (pin "6") (pinfunction "BISEN_6") (pintype "passive"))
      (node (ref "U7") (pin "2") (pinfunction "GND_2") (pintype "passive"))
    )
    (net (code "42") (name "Net-(C18-Pad1)") (class "Default")
      (node (ref "C18") (pin "1") (pinfunction "1_1") (pintype "passive"))
      (node (ref "R9") (pin "2") (pinfunction "2_2") (pintype "passive"))
    )
    (net (code "43") (name "Net-(D1-K)") (class "Default")
      (node (ref "C4") (pin "2") (pinfunction "2_2") (pintype "passive"))
      (node (ref "D1") (pin "2") (pinfunction "K_2") (pintype "passive"))
      (node (ref "L1") (pin "1") (pintype "passive"))
      (node (ref "U2") (pin "8") (pinfunction "SW_8") (pintype "output"))
    )
    (net (code "44") (name "Net-(DL1-K)") (class "Default")
      (node (ref "DL1") (pin "1") (pinfunction "K_1") (pintype "passive"))
      (node (ref "R4") (pin "1") (pinfunction "1_1") (pintype "passive"))
    )
    (net (code "45") (name "Net-(DL2-K)") (class "Default")
      (node (ref "DL2") (pin "1") (pinfunction "K_1") (pintype "passive"))
      (node (ref "R5") (pin "1") (pinfunction "1_1") (pintype "passive"))
    )
    (net (code "46") (name "Net-(F1-Pad2)") (class "Default")
      (node (ref "F1") (pin "2") (pinfunction "2_2") (pintype "passive"))
      (node (ref "Q1") (pin "3") (pinfunction "3_3") (pintype "passive"))
    )
    (net (code "47") (name "Net-(H1-VBATT)") (class "Default")
      (node (ref "F1") (pin "1") (pinfunction "1_1") (pintype "passive"))
      (node (ref "H1") (pin "2") (pinfunction "VBATT_2") (pintype "passive"))
    )
    (net (code "48") (name "Net-(U1A-DDM{slash}PB10)") (class "Default")
      (node (ref "R2") (pin "2") (pinfunction "2_2") (pintype "passive"))
      (node (ref "U1") (pin "56") (pinfunction "DDM/PB10_56") (pintype "bidirectional"))
    )
    (net (code "49") (name "Net-(U1A-DDP{slash}PB11)") (class "Default")
      (node (ref "R1") (pin "2") (pinfunction "2_2") (pintype "passive"))
      (node (ref "U1") (pin "57") (pinfunction "DDP/PB11_57") (pintype "bidirectional"))
    )
    (net (code "50") (name "Net-(U1A-ERASE{slash}PB12)") (class "Default")
      (node (ref "TP2") (pin "1") (pinfunction "1_1") (pintype "passive"))
      (node (ref "U1") (pin "55") (pinfunction "ERASE/PB12_55") (pintype "bidirectional"))
    )
    (net (code "51") (name "Net-(U1A-XIN{slash}PGMCK{slash}PB9)") (class "Default")
      (node (ref "C1") (pin "2") (pinfunction "2_2") (pintype "passive"))
      (node (ref "U1") (pin "62") (pinfunction "XIN/PGMCK/PB9_62") (pintype "bidirectional"))
      (node (ref "Y1") (pin "1") (pinfunction "OSC1_1") (pintype "passive"))
    )
    (net (code "52") (name "Net-(U1A-XOUT{slash}PB8)") (class "Default")
      (node (ref "C2") (pin "2") (pinfunction "2_2") (pintype "passive"))
      (node (ref "U1") (pin "61") (pinfunction "XOUT/PB8_61") (pintype "bidirectional"))
      (node (ref "Y1") (pin "3") (pinfunction "OSC2_3") (pintype "passive"))
    )
    (net (code "53") (name "Net-(U1B-VDDOUT)") (class "Default")
      (node (ref "C10") (pin "1") (pinfunction "1_1") (pintype "passive"))
      (node (ref "C12") (pin "1") (pinfunction "1_1") (pintype "passive"))
      (node (ref "C15") (pin "1") (pinfunction "1_1") (pintype "passive"))
      (node (ref "C8") (pin "1") (pinfunction "1_1") (pintype "passive"))
      (node (ref "L2") (pin "2") (pinfunction "2_2") (pintype "passive"))
      (node (ref "U1") (pin "12") (pinfunction "VDDCORE_12") (pintype "power_in"))
      (node (ref "U1") (pin "24") (pinfunction "VDDCORE_24") (pintype "power_in"))
      (node (ref "U1") (pin "54") (pinfunction "VDDCORE_54") (pintype "power_in"))
      (node (ref "U1") (pin "8") (pinfunction "VDDOUT_8") (pintype "power_in"))
    )
    (net (code "54") (name "Net-(U1B-VDDPLL)") (class "Default")
      (node (ref "C17") (pin "2") (pinfunction "2_2") (pintype "passive"))
      (node (ref "C18") (pin "2") (pinfunction "2_2") (pintype "passive"))
      (node (ref "L2") (pin "1") (pinfunction "1_1") (pintype "passive"))
      (node (ref "U1") (pin "64") (pinfunction "VDDPLL_64") (pintype "power_in"))
    )
    (net (code "55") (name "Net-(U2-BST)") (class "Default")
      (node (ref "C4") (pin "1") (pinfunction "1_1") (pintype "passive"))
      (node (ref "U2") (pin "1") (pinfunction "BST_1") (pintype "passive"))
    )
    (net (code "56") (name "Net-(U2-PGOOD)") (class "Default")
      (node (ref "R3") (pin "1") (pinfunction "1_1") (pintype "passive"))
      (node (ref "U2") (pin "4") (pinfunction "PGOOD_4") (pintype "output"))
    )
    (net (code "57") (name "Net-(U3-VCC)") (class "Default")
      (node (ref "C13") (pin "2") (pinfunction "2_2") (pintype "passive"))
      (node (ref "R6") (pin "2") (pinfunction "2_2") (pintype "passive"))
      (node (ref "U3") (pin "1") (pinfunction "VCC_1") (pintype "passive"))
    )
    (net (code "58") (name "Net-(U4-OUT)") (class "Default")
      (node (ref "C20") (pin "2") (pinfunction "2_2") (pintype "passive"))
      (node (ref "R18") (pin "1") (pinfunction "1_1") (pintype "passive"))
      (node (ref "U4") (pin "5") (pinfunction "OUT_5") (pintype "power_in"))
    )
    (net (code "59") (name "Net-(U6-VCP)") (class "Default")
      (node (ref "C24") (pin "2") (pinfunction "2_2") (pintype "passive"))
      (node (ref "U6") (pin "11") (pinfunction "VCP_11") (pintype "passive"))
    )
    (net (code "60") (name "Net-(U6-VINT)") (class "Default")
      (node (ref "C25") (pin "1") (pinfunction "1_1") (pintype "passive"))
      (node (ref "U6") (pin "14") (pinfunction "VINT_14") (pintype "passive"))
    )
    (net (code "61") (name "Net-(U6-VM)") (class "Default")
      (node (ref "C23") (pin "1") (pinfunction "1_1") (pintype "passive"))
      (node (ref "C24") (pin "1") (pinfunction "1_1") (pintype "passive"))
      (node (ref "R16") (pin "1") (pinfunction "1_1") (pintype "passive"))
      (node (ref "R17") (pin "1") (pinfunction "1_1") (pintype "passive"))
      (node (ref "U6") (pin "12") (pinfunction "VM_12") (pintype "passive"))
    )
    (net (code "62") (name "USB_DETECT") (class "Default")
      (node (ref "R7") (pin "1") (pinfunction "1_1") (pintype "passive"))
      (node (ref "R8") (pin "2") (pinfunction "2_2") (pintype "passive"))
      (node (ref "U1") (pin "35") (pinfunction "PA5/PGMRDY_35") (pintype "bidirectional"))
      (node (ref "USB_DETECT_TP") (pin "1") (pinfunction "1_1") (pintype "passive"))
    )
    (net (code "63") (name "VBUS") (class "Default")
      (node (ref "D2") (pin "1") (pinfunction "A_1") (pintype "passive"))
      (node (ref "H3") (pin "1") (pinfunction "VBUS_1") (pintype "power_in"))
      (node (ref "R7") (pin "2") (pinfunction "2_2") (pintype "passive"))
      (node (ref "VBUS_TP") (pin "1") (pinfunction "1_1") (pintype "passive"))
    )
    (net (code "64") (name "V_BAT") (class "Default")
      (node (ref "C3") (pin "2") (pinfunction "2_2") (pintype "passive"))
      (node (ref "Q1") (pin "2") (pinfunction "2_2") (pintype "passive"))
      (node (ref "R14") (pin "2") (pinfunction "2_2") (pintype "passive"))
      (node (ref "R16") (pin "2") (pinfunction "2_2") (pintype "passive"))
      (node (ref "R17") (pin "2") (pinfunction "2_2") (pintype "passive"))
      (node (ref "R3") (pin "2") (pinfunction "2_2") (pintype "passive"))
      (node (ref "U2") (pin "2") (pinfunction "VIN_2") (pintype "input"))
      (node (ref "U2") (pin "3") (pinfunction "EN_3") (pintype "output"))
      (node (ref "V_BATT_TP") (pin "1") (pinfunction "1_1") (pintype "passive"))
    )
    (net (code "65") (name "nRST") (class "Default")
      (node (ref "H2") (pin "1") (pinfunction "1_1") (pintype "passive"))
      (node (ref "S1") (pin "1") (pintype "passive"))
      (node (ref "U1") (pin "39") (pinfunction "NRST_39") (pintype "bidirectional"))
      (node (ref "nRST_TP") (pin "1") (pinfunction "1_1") (pintype "passive"))
    )
    (net (code "66") (name "unconnected-(H2-Pad3)") (class "Default")
      (node (ref "H2") (pin "3") (pinfunction "3_3") (pintype "passive+no_connect"))
    )
    (net (code "67") (name "unconnected-(H2-Pad9)") (class "Default")
      (node (ref "H2") (pin "9") (pinfunction "9_9") (pintype "passive+no_connect"))
    )
    (net (code "68") (name "unconnected-(H2-Pad10)") (class "Default")
      (node (ref "H2") (pin "10") (pinfunction "10_10") (pintype "passive+no_connect"))
    )
    (net (code "69") (name "unconnected-(H3-ID-Pad4)") (class "Default")
      (node (ref "H3") (pin "4") (pinfunction "ID_4") (pintype "power_in"))
    )
    (net (code "70") (name "unconnected-(H13-Pad8)") (class "Default")
      (node (ref "H13") (pin "8") (pinfunction "8_8") (pintype "passive+no_connect"))
    )
    (net (code "71") (name "unconnected-(U1A-JTAGSEL-Pad50)") (class "Default")
      (node (ref "U1") (pin "50") (pinfunction "JTAGSEL_50") (pintype "input+no_connect"))
    )
    (net (code "72") (name "unconnected-(U1A-PA6{slash}PGMNOE-Pad34)") (class "Default")
      (node (ref "U1") (pin "34") (pinfunction "PA6/PGMNOE_34") (pintype "bidirectional+no_connect"))
    )
    (net (code "73") (name "unconnected-(U1A-PA9{slash}PGMM1-Pad30)") (class "Default")
      (node (ref "U1") (pin "30") (pinfunction "PA9/PGMM1_30") (pintype "bidirectional+no_connect"))
    )
    (net (code "74") (name "unconnected-(U1A-PA10{slash}PGMM2-Pad29)") (class "Default")
      (node (ref "U1") (pin "29") (pinfunction "PA10/PGMM2_29") (pintype "bidirectional+no_connect"))
    )
    (net (code "75") (name "unconnected-(U1A-PA16{slash}PGMD4-Pad19)") (class "Default")
      (node (ref "U1") (pin "19") (pinfunction "PA16/PGMD4_19") (pintype "bidirectional+no_connect"))
    )
    (net (code "76") (name "unconnected-(U1A-PA21{slash}PGMD9{slash}AD8-Pad11)") (class "Default")
      (node (ref "U1") (pin "11") (pinfunction "PA21/PGMD9/AD8_11") (pintype "bidirectional+no_connect"))
    )
    (net (code "77") (name "unconnected-(U1A-PA22{slash}PGMD10{slash}AD9-Pad14)") (class "Default")
      (node (ref "U1") (pin "14") (pinfunction "PA22/PGMD10/AD9_14") (pintype "bidirectional+no_connect"))
    )
    (net (code "78") (name "unconnected-(U1A-PA25{slash}PGMD13-Pad25)") (class "Default")
      (node (ref "U1") (pin "25") (pinfunction "PA25/PGMD13_25") (pintype "bidirectional+no_connect"))
    )
    (net (code "79") (name "unconnected-(U1A-PA26{slash}PGMD14-Pad26)") (class "Default")
      (node (ref "U1") (pin "26") (pinfunction "PA26/PGMD14_26") (pintype "bidirectional+no_connect"))
    )
    (net (code "80") (name "unconnected-(U1A-PB1{slash}AD5-Pad4)") (class "Default")
      (node (ref "U1") (pin "4") (pinfunction "PB1/AD5_4") (pintype "bidirectional+no_connect"))
    )
    (net (code "81") (name "unconnected-(U1A-PB2{slash}AD6-Pad5)") (class "Default")
      (node (ref "U1") (pin "5") (pinfunction "PB2/AD6_5") (pintype "bidirectional+no_connect"))
    )
    (net (code "82") (name "unconnected-(U1A-PB3{slash}AD7-Pad6)") (class "Default")
      (node (ref "U1") (pin "6") (pinfunction "PB3/AD7_6") (pintype "bidirectional+no_connect"))
    )
    (net (code "83") (name "unconnected-(U1A-TDI{slash}PB4-Pad33)") (class "Default")
      (node (ref "U1") (pin "33") (pinfunction "TDI/PB4_33") (pintype "bidirectional+no_connect"))
    )
    (net (code "84") (name "unconnected-(U1A-TDO{slash}TRACESWO{slash}PB5-Pad49)") (class "Default")
      (node (ref "U1") (pin "49") (pinfunction "TDO/TRACESWO/PB5_49") (pintype "bidirectional+no_connect"))
    )
    (net (code "85") (name "unconnected-(U1A-TST-Pad40)") (class "Default")
      (node (ref "U1") (pin "40") (pinfunction "TST_40") (pintype "input+no_connect"))
    )
    (net (code "86") (name "unconnected-(U2-NC-Pad6)") (class "Default")
      (node (ref "U2") (pin "6") (pinfunction "NC_6") (pintype "passive+no_connect"))
    )
    (net (code "87") (name "unconnected-(U4-BYP-Pad4)") (class "Default")
      (node (ref "U4") (pin "4") (pinfunction "BYP_4") (pintype "passive"))
    )
    (net (code "88") (name "unconnected-(U5-BYP-Pad4)") (class "Default")
      (node (ref "U5") (pin "4") (pinfunction "BYP_4") (pintype "passive"))
    )
  )
)
